# Blink_Blink_Beep_Boop.net
KiCad netlist of a schematic drawn in Altium Designer
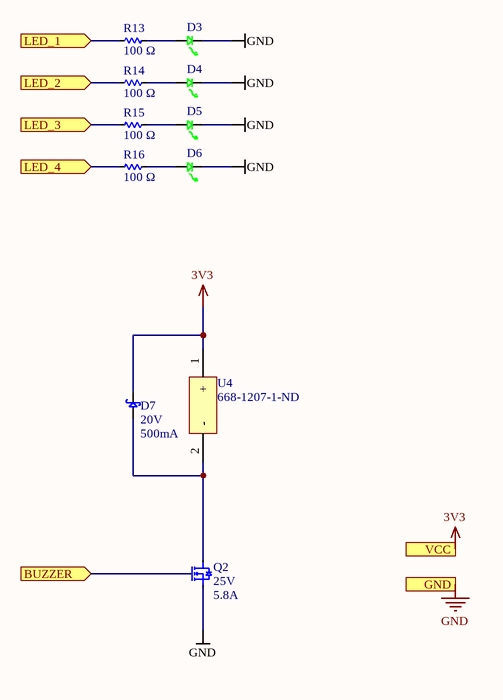
[diagram p0: Blink_Blink_Beep_Boop.SchDoc]

(export (version "E")
  (design (tool "Eeschema 10.0.6"))
  (components
    (comp (ref "D3")
      (value "GREEN")
      (footprint "0805_Diode")
      (description "LED 0805 GREEN 20MA")
      (fields
        (field (name "MANUFACTURER") "OSRAM Opto Semiconductors Inc")
        (field (name "MANUFACTURER PART NUMBER") "LG R971-KN-1")
      )
      (libsource (lib "SSI") (part "LED_LY971"))
    )
    (comp (ref "D4")
      (value "GREEN")
      (footprint "0805_Diode")
      (description "LED 0805 GREEN 20MA")
      (fields
        (field (name "MANUFACTURER") "OSRAM Opto Semiconductors Inc")
        (field (name "MANUFACTURER PART NUMBER") "LG R971-KN-1")
      )
      (libsource (lib "SSI") (part "LED_LY971"))
    )
    (comp (ref "D5")
      (value "GREEN")
      (footprint "0805_Diode")
      (description "LED 0805 GREEN 20MA")
      (fields
        (field (name "MANUFACTURER") "OSRAM Opto Semiconductors Inc")
        (field (name "MANUFACTURER PART NUMBER") "LG R971-KN-1")
      )
      (libsource (lib "SSI") (part "LED_LY971"))
    )
    (comp (ref "D6")
      (value "GREEN")
      (footprint "0805_Diode")
      (description "LED 0805 GREEN 20MA")
      (fields
        (field (name "MANUFACTURER") "OSRAM Opto Semiconductors Inc")
        (field (name "MANUFACTURER PART NUMBER") "LG R971-KN-1")
      )
      (libsource (lib "SSI") (part "LED_LY971"))
    )
    (comp (ref "D7")
      (value "SCHOTTKY_MBR0520L")
      (footprint "SOD123")
      (description "DIODE SCHOTTKY 0.5A 20V SOD-123")
      (fields
        (field (name "MANUFACTURER") "Fairchild Semiconductor")
        (field (name "MANUFACTURER PART NUMBER") "MBR0520L")
        (field (name "VOLTAGE - DC REVERSE (VR) (MAX)") "20V")
        (field (name "CURRENT - AVERAGE RECTIFIED (IO)") "500mA")
      )
      (libsource (lib "SSI") (part "SCHOTTKY_MBR0520L"))
    )
    (comp (ref "Q2")
      (value "MOSFET N-CH 60V 1.7A SSOT3")
      (footprint "3SOT23")
      (description "MOSFET N-CH 25V 5.8A SOT23")
      (fields
        (field (name "MANUFACTURER") "International Rectifier")
        (field (name "MANUFACTURER PART NUMBER") "IRFML8244TRPBF")
        (field (name "DRAIN TO SOURCE VOLTAGE (VDSS)") "25V")
        (field (name "CURRENT - CONTINUOUS DRAIN (ID) @ 25° C") "5.8A")
      )
      (libsource (lib "SSI") (part "NFET_IRFML8244TRPBF"))
    )
    (comp (ref "R13")
      (value "__template_resistor")
      (footprint "R0603")
      (fields
        (field (name "MANUFACTURER PART NUMBER") "RC0603FR-07100RL")
        (field (name "MANUFACTURER") "Yageo")
        (field (name "TOLERANCE") "±1%")
        (field (name "RESISTANCE") "100 Ω")
      )
      (libsource (lib "passives") (part "__template_resistor"))
    )
    (comp (ref "R14")
      (value "__template_resistor")
      (footprint "R0603")
      (fields
        (field (name "MANUFACTURER PART NUMBER") "RC0603FR-07100RL")
        (field (name "MANUFACTURER") "Yageo")
        (field (name "TOLERANCE") "±1%")
        (field (name "RESISTANCE") "100 Ω")
      )
      (libsource (lib "passives") (part "__template_resistor"))
    )
    (comp (ref "R15")
      (value "__template_resistor")
      (footprint "R0603")
      (fields
        (field (name "MANUFACTURER PART NUMBER") "RC0603FR-07100RL")
        (field (name "MANUFACTURER") "Yageo")
        (field (name "TOLERANCE") "±1%")
        (field (name "RESISTANCE") "100 Ω")
      )
      (libsource (lib "passives") (part "__template_resistor"))
    )
    (comp (ref "R16")
      (value "__template_resistor")
      (footprint "R0603")
      (fields
        (field (name "MANUFACTURER PART NUMBER") "RC0603FR-07100RL")
        (field (name "MANUFACTURER") "Yageo")
        (field (name "TOLERANCE") "±1%")
        (field (name "RESISTANCE") "100 Ω")
      )
      (libsource (lib "passives") (part "__template_resistor"))
    )
    (comp (ref "U4")
      (value "BUZ_SMT-0540-T-7-R")
      (footprint "BUZ_SMT-0540-T-7-R")
      (description "Peak-Peak Signal Buzzer Single Tone 4kHz Magnetic 2 ~ 4V 78dB @ 3V, 10cm")
      (fields
        (field (name "MANUFACTURER") "PUI Audio, Inc.")
        (field (name "MANUFACTURER PART NUMBER") "SMT-0540-T-7-R")
        (field (name "SUPPLIER PART NUMBER 1") "668-1207-1-ND")
      )
      (libsource (lib "SSI") (part "BUZ_SMT-0540-T-7-R"))
    )
  )
  (nets
    (net (code "1") (name "/BUZZER") (class "Default") (node (ref "Q2") (pin "1") (pintype "passive")))
    (net (code "2") (name "/LED_1") (class "Default") (node (ref "R13") (pin "1") (pintype "passive")))
    (net (code "3") (name "/LED_2") (class "Default") (node (ref "R14") (pin "1") (pintype "passive")))
    (net (code "4") (name "/LED_3") (class "Default") (node (ref "R15") (pin "1") (pintype "passive")))
    (net (code "5") (name "/LED_4") (class "Default") (node (ref "R16") (pin "1") (pintype "passive")))
    (net (code "6") (name "3V3") (class "Default")
      (node (ref "D7") (pin "2") (pintype "passive"))
      (node (ref "U4") (pin "1") (pinfunction "+_1") (pintype "passive"))
    )
    (net (code "7") (name "GND") (class "Default")
      (node (ref "D3") (pin "1") (pintype "passive"))
      (node (ref "D4") (pin "1") (pintype "passive"))
      (node (ref "D5") (pin "1") (pintype "passive"))
      (node (ref "D6") (pin "1") (pintype "passive"))
      (node (ref "Q2") (pin "2") (pintype "passive"))
    )
    (net (code "8") (name "Net-(D3-Pad2)") (class "Default")
      (node (ref "D3") (pin "2") (pintype "passive"))
      (node (ref "R13") (pin "2") (pintype "passive"))
    )
    (net (code "9") (name "Net-(D4-Pad2)") (class "Default")
      (node (ref "D4") (pin "2") (pintype "passive"))
      (node (ref "R14") (pin "2") (pintype "passive"))
    )
    (net (code "10") (name "Net-(D5-Pad2)") (class "Default")
      (node (ref "D5") (pin "2") (pintype "passive"))
      (node (ref "R15") (pin "2") (pintype "passive"))
    )
    (net (code "11") (name "Net-(D6-Pad2)") (class "Default")
      (node (ref "D6") (pin "2") (pintype "passive"))
      (node (ref "R16") (pin "2") (pintype "passive"))
    )
    (net (code "12") (name "Net-(U4--)") (class "Default")
      (node (ref "D7") (pin "1") (pintype "passive"))
      (node (ref "Q2") (pin "3") (pintype "passive"))
      (node (ref "U4") (pin "2") (pinfunction "-_2") (pintype "passive"))
    )
  )
)
